# Control_board_POD_CMS.net
KiCad netlist of a schematic drawn in EAGLE
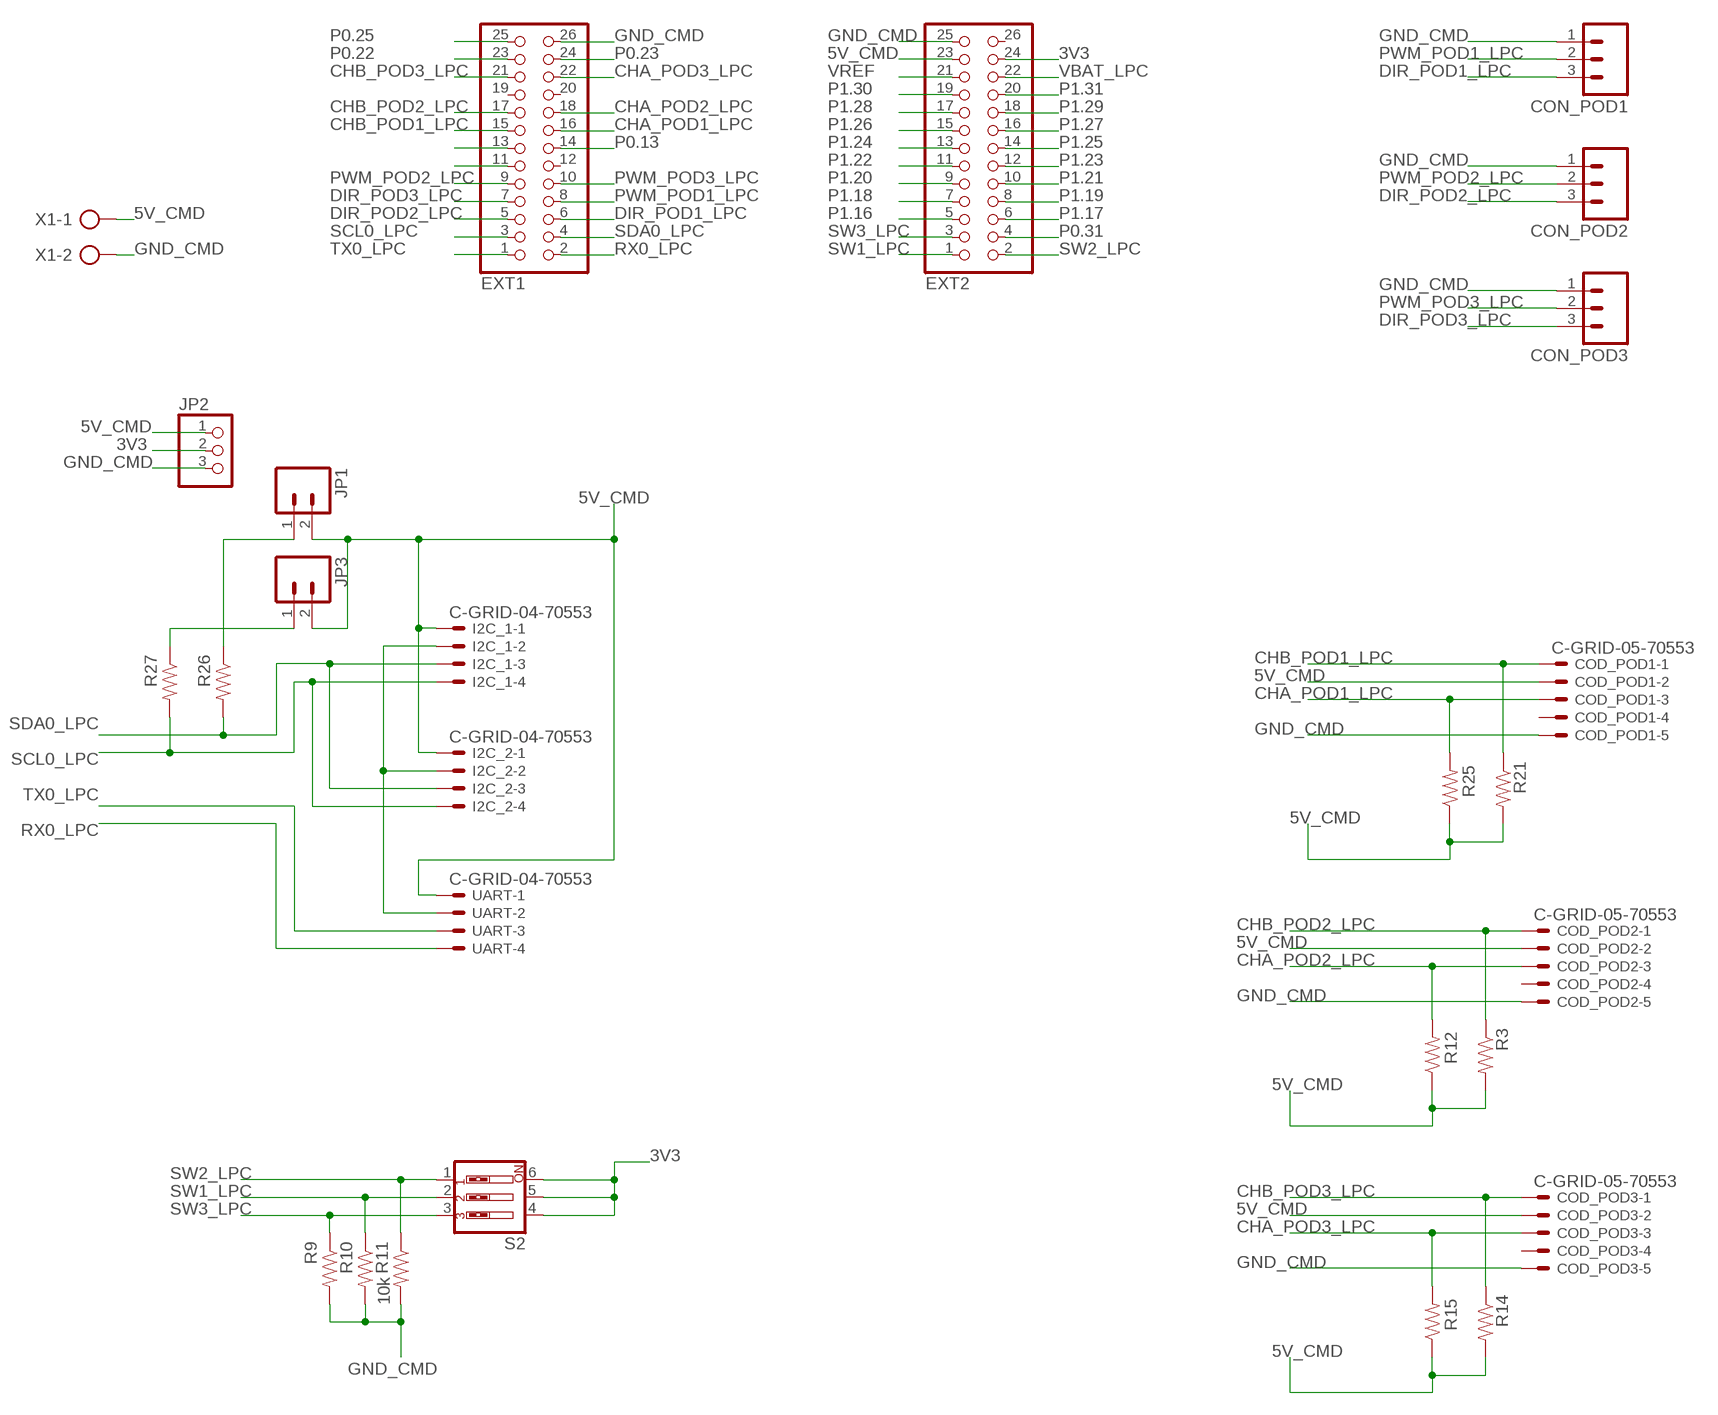
[diagram p0: schematic, sheet 1, part 1 of 2]
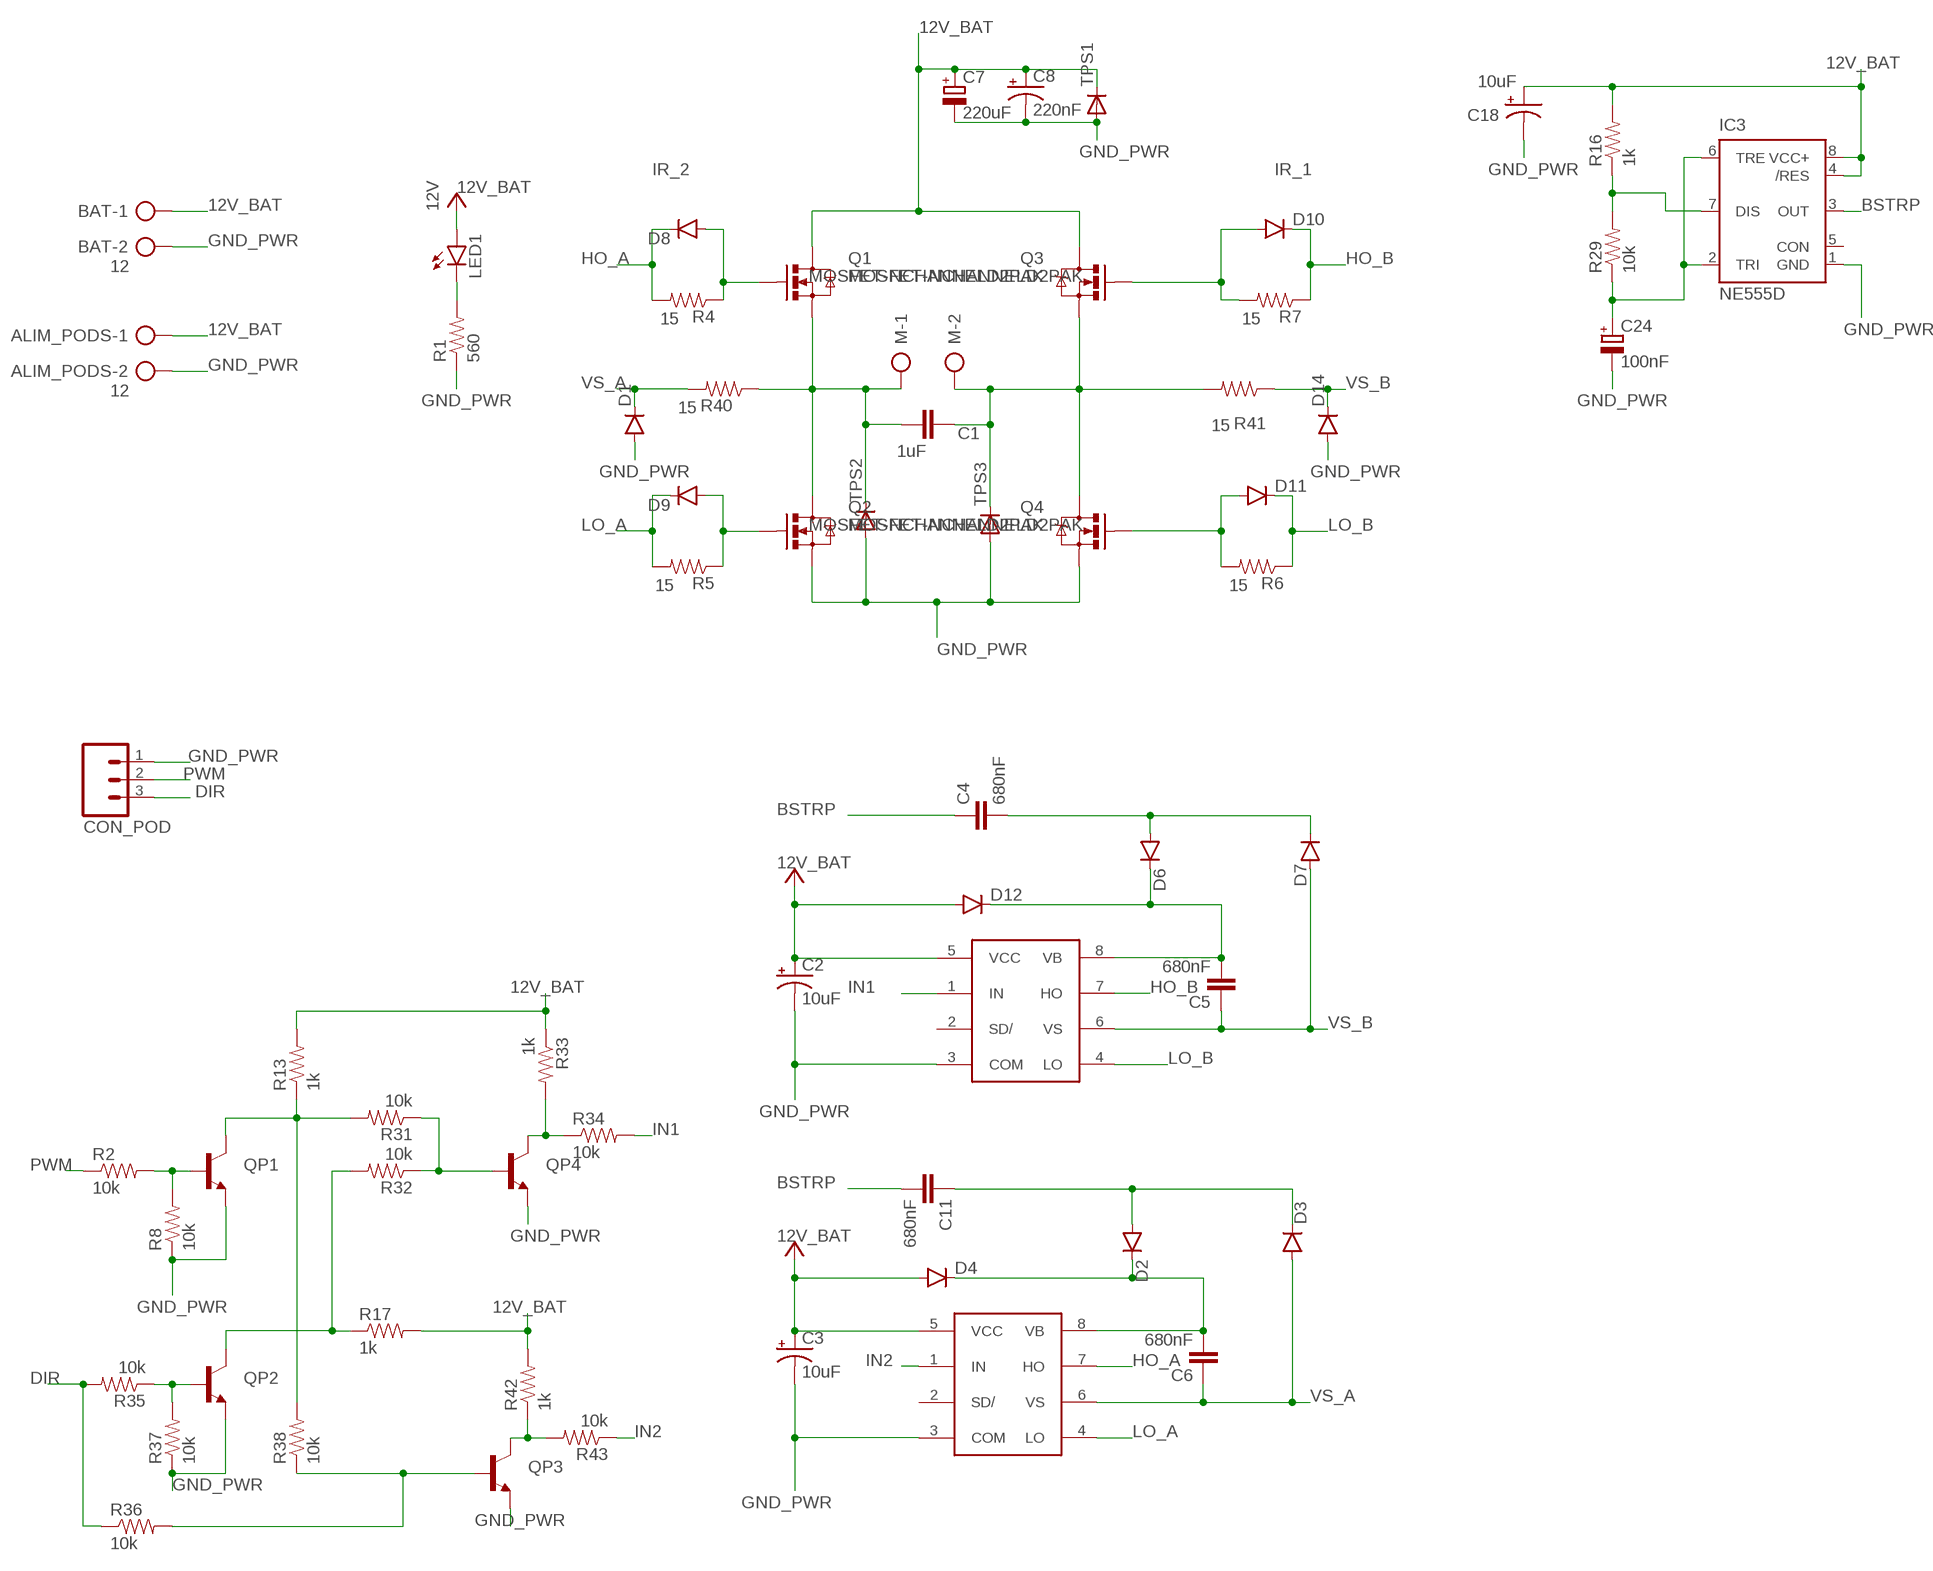
[diagram p1: schematic, sheet 1, part 2 of 2]

(export (version "E")
  (design (tool "Eeschema 10.0.6"))
  (components
    (comp (ref "ALIM_PODS")
      (value "12")
      (footprint "eagle-import:AK500_2")
      (libsource (lib "eagle-import") (part "AK500/2"))
    )
    (comp (ref "BAT")
      (value "12")
      (footprint "eagle-import:AK500_2")
      (libsource (lib "eagle-import") (part "AK500/2"))
    )
    (comp (ref "C1")
      (value "1uF")
      (footprint "eagle-import:0603-CAP")
      (libsource (lib "eagle-import") (part "CAP0603-CAP"))
    )
    (comp (ref "C2")
      (value "10uF")
      (footprint "eagle-import:EIA3216")
      (libsource (lib "eagle-import") (part "10UF-16V-10%(TANT)"))
    )
    (comp (ref "C3")
      (value "10uF")
      (footprint "eagle-import:EIA3216")
      (libsource (lib "eagle-import") (part "10UF-16V-10%(TANT)"))
    )
    (comp (ref "C4")
      (value "680nF")
      (footprint "eagle-import:0805")
      (libsource (lib "eagle-import") (part "SparkFun-Capacitors_CAP0805"))
    )
    (comp (ref "C5")
      (value "680nF")
      (footprint "eagle-import:1206")
      (libsource (lib "eagle-import") (part "SparkFun-Capacitors_CAP1206"))
    )
    (comp (ref "C6")
      (value "680nF")
      (footprint "eagle-import:1206")
      (libsource (lib "eagle-import") (part "SparkFun-Capacitors_CAP1206"))
    )
    (comp (ref "C7")
      (value "220uF")
      (footprint "eagle-import:D_7343-31R")
      (libsource (lib "eagle-import") (part "CPOL-EUD/7343-31R"))
    )
    (comp (ref "C8")
      (value "220nF")
      (footprint "eagle-import:EIA3216")
      (libsource (lib "eagle-import") (part "10UF-16V-10%(TANT)"))
    )
    (comp (ref "C11")
      (value "680nF")
      (footprint "eagle-import:0805")
      (libsource (lib "eagle-import") (part "SparkFun-Capacitors_CAP0805"))
    )
    (comp (ref "C18")
      (value "10uF")
      (footprint "eagle-import:EIA3216")
      (fields (field (name "PROD_ID") "CAP-00811"))
      (libsource (lib "eagle-import") (part "10UF-16V-10%(TANT)"))
    )
    (comp (ref "C24")
      (value "100nF")
      (footprint "eagle-import:R_2012-12R")
      (libsource (lib "eagle-import") (part "CPOL-EUR/2012-12R"))
    )
    (comp (ref "COD_POD1")
      (value "C-GRID-05-70553")
      (footprint "eagle-import:70553-05")
      (libsource (lib "eagle-import") (part "C-GRID-05-70553"))
    )
    (comp (ref "COD_POD2")
      (value "C-GRID-05-70553")
      (footprint "eagle-import:70553-05")
      (libsource (lib "eagle-import") (part "C-GRID-05-70553"))
    )
    (comp (ref "COD_POD3")
      (value "C-GRID-05-70553")
      (footprint "eagle-import:70553-05")
      (libsource (lib "eagle-import") (part "C-GRID-05-70553"))
    )
    (comp (ref "CON_POD")
      (value "M03PTH")
      (footprint "eagle-import:1X03")
      (libsource (lib "eagle-import") (part "M03PTH"))
    )
    (comp (ref "CON_POD1")
      (value "M03PTH")
      (footprint "eagle-import:1X03")
      (libsource (lib "eagle-import") (part "M03PTH"))
    )
    (comp (ref "CON_POD2")
      (value "M03PTH")
      (footprint "eagle-import:1X03")
      (libsource (lib "eagle-import") (part "M03PTH"))
    )
    (comp (ref "CON_POD3")
      (value "M03PTH")
      (footprint "eagle-import:1X03")
      (libsource (lib "eagle-import") (part "M03PTH"))
    )
    (comp (ref "D1")
      (value "DIODESOD")
      (footprint "eagle-import:SOD-323")
      (libsource (lib "eagle-import") (part "DIODESOD"))
    )
    (comp (ref "D2")
      (value "DIODESOD")
      (footprint "eagle-import:SOD-323")
      (libsource (lib "eagle-import") (part "DIODESOD"))
    )
    (comp (ref "D3")
      (value "DIODESOD")
      (footprint "eagle-import:SOD-323")
      (libsource (lib "eagle-import") (part "DIODESOD"))
    )
    (comp (ref "D4")
      (value "DIODESOD")
      (footprint "eagle-import:SOD-323")
      (libsource (lib "eagle-import") (part "DIODESOD"))
    )
    (comp (ref "D6")
      (value "DIODESOD")
      (footprint "eagle-import:SOD-323")
      (libsource (lib "eagle-import") (part "DIODESOD"))
    )
    (comp (ref "D7")
      (value "DIODESOD")
      (footprint "eagle-import:SOD-323")
      (libsource (lib "eagle-import") (part "DIODESOD"))
    )
    (comp (ref "D8")
      (value "DIODESOD")
      (footprint "eagle-import:SOD-323")
      (libsource (lib "eagle-import") (part "DIODESOD"))
    )
    (comp (ref "D9")
      (value "DIODESOD")
      (footprint "eagle-import:SOD-323")
      (libsource (lib "eagle-import") (part "DIODESOD"))
    )
    (comp (ref "D10")
      (value "DIODESOD")
      (footprint "eagle-import:SOD-323")
      (libsource (lib "eagle-import") (part "DIODESOD"))
    )
    (comp (ref "D11")
      (value "DIODESOD")
      (footprint "eagle-import:SOD-323")
      (libsource (lib "eagle-import") (part "DIODESOD"))
    )
    (comp (ref "D12")
      (value "DIODESOD")
      (footprint "eagle-import:SOD-323")
      (libsource (lib "eagle-import") (part "DIODESOD"))
    )
    (comp (ref "D14")
      (value "DIODESOD")
      (footprint "eagle-import:SOD-323")
      (libsource (lib "eagle-import") (part "DIODESOD"))
    )
    (comp (ref "EXT1")
      (value "PINHD-2X13")
      (footprint "eagle-import:2X13")
      (libsource (lib "eagle-import") (part "PINHD-2X13"))
    )
    (comp (ref "EXT2")
      (value "PINHD-2X13")
      (footprint "eagle-import:2X13")
      (libsource (lib "eagle-import") (part "PINHD-2X13"))
    )
    (comp (ref "I2C_1")
      (value "C-GRID-04-70553")
      (footprint "eagle-import:70553-04")
      (libsource (lib "eagle-import") (part "C-GRID-04-70553"))
    )
    (comp (ref "I2C_2")
      (value "C-GRID-04-70553")
      (footprint "eagle-import:70553-04")
      (libsource (lib "eagle-import") (part "C-GRID-04-70553"))
    )
    (comp (ref "IC3")
      (value "NE555D")
      (footprint "eagle-import:SO08")
      (libsource (lib "eagle-import") (part "NE555D"))
    )
    (comp (ref "IR2184SPBF1")
      (value "IR2184SPBF")
      (footprint "eagle-import:SO08")
      (libsource (lib "eagle-import") (part "IR2184SPBF"))
    )
    (comp (ref "IR2184SPBF2")
      (value "IR2184SPBF")
      (footprint "eagle-import:SO08")
      (libsource (lib "eagle-import") (part "IR2184SPBF"))
    )
    (comp (ref "JP1")
      (value "M02PTH")
      (footprint "eagle-import:1X02")
      (libsource (lib "eagle-import") (part "M02PTH"))
    )
    (comp (ref "JP2")
      (value "PINHD-1X3")
      (footprint "eagle-import:1X03")
      (libsource (lib "eagle-import") (part "PINHD-1X3"))
    )
    (comp (ref "JP3")
      (value "M02PTH")
      (footprint "eagle-import:1X02")
      (libsource (lib "eagle-import") (part "M02PTH"))
    )
    (comp (ref "LED1")
      (value "LED-WHITE")
      (footprint "eagle-import:LED-1206")
      (libsource (lib "eagle-import") (part "LED-WHITE"))
    )
    (comp (ref "M")
      (value "AK500/2")
      (footprint "eagle-import:AK500_2")
      (libsource (lib "eagle-import") (part "AK500/2"))
    )
    (comp (ref "Q1")
      (value "MOSFET-NCHANNELD2PAK")
      (footprint "eagle-import:D2PAK-3")
      (libsource (lib "eagle-import") (part "MOSFET-NCHANNELD2PAK"))
    )
    (comp (ref "Q2")
      (value "MOSFET-NCHANNELD2PAK")
      (footprint "eagle-import:D2PAK-3")
      (libsource (lib "eagle-import") (part "MOSFET-NCHANNELD2PAK"))
    )
    (comp (ref "Q3")
      (value "MOSFET-NCHANNELD2PAK")
      (footprint "eagle-import:D2PAK-3")
      (libsource (lib "eagle-import") (part "MOSFET-NCHANNELD2PAK"))
    )
    (comp (ref "Q4")
      (value "MOSFET-NCHANNELD2PAK")
      (footprint "eagle-import:D2PAK-3")
      (libsource (lib "eagle-import") (part "MOSFET-NCHANNELD2PAK"))
    )
    (comp (ref "QP1")
      (value "TRANSISTOR_NPNSOT23-3")
      (footprint "eagle-import:SOT23-3")
      (libsource (lib "eagle-import") (part "TRANSISTOR_NPNSOT23-3"))
    )
    (comp (ref "QP2")
      (value "TRANSISTOR_NPNSOT23-3")
      (footprint "eagle-import:SOT23-3")
      (libsource (lib "eagle-import") (part "TRANSISTOR_NPNSOT23-3"))
    )
    (comp (ref "QP3")
      (value "TRANSISTOR_NPNSOT23-3")
      (footprint "eagle-import:SOT23-3")
      (libsource (lib "eagle-import") (part "TRANSISTOR_NPNSOT23-3"))
    )
    (comp (ref "QP4")
      (value "TRANSISTOR_NPNSOT23-3")
      (footprint "eagle-import:SOT23-3")
      (libsource (lib "eagle-import") (part "TRANSISTOR_NPNSOT23-3"))
    )
    (comp (ref "R1")
      (value "560")
      (footprint "eagle-import:1206")
      (libsource (lib "eagle-import") (part "RESISTOR1206"))
    )
    (comp (ref "R2")
      (value "10k")
      (footprint "eagle-import:0603-RES")
      (libsource (lib "eagle-import") (part "SparkFun-Passives_RESISTOR0603-RES"))
    )
    (comp (ref "R3")
      (value "3k3")
      (footprint "eagle-import:0603-RES")
      (libsource (lib "eagle-import") (part "SparkFun-Passives_RESISTOR0603-RES"))
    )
    (comp (ref "R4")
      (value "15")
      (footprint "eagle-import:0805")
      (libsource (lib "eagle-import") (part "SparkFun-Passives_RESISTOR0805-RES"))
    )
    (comp (ref "R5")
      (value "15")
      (footprint "eagle-import:0805")
      (libsource (lib "eagle-import") (part "SparkFun-Passives_RESISTOR0805-RES"))
    )
    (comp (ref "R6")
      (value "15")
      (footprint "eagle-import:0805")
      (libsource (lib "eagle-import") (part "SparkFun-Passives_RESISTOR0805-RES"))
    )
    (comp (ref "R7")
      (value "15")
      (footprint "eagle-import:0805")
      (libsource (lib "eagle-import") (part "SparkFun-Passives_RESISTOR0805-RES"))
    )
    (comp (ref "R8")
      (value "10k")
      (footprint "eagle-import:0603-RES")
      (libsource (lib "eagle-import") (part "SparkFun-Passives_RESISTOR0603-RES"))
    )
    (comp (ref "R9")
      (value "10k")
      (footprint "eagle-import:0603-RES")
      (libsource (lib "eagle-import") (part "SparkFun-Passives_RESISTOR0603-RES"))
    )
    (comp (ref "R10")
      (value "10k")
      (footprint "eagle-import:0603-RES")
      (libsource (lib "eagle-import") (part "SparkFun-Passives_RESISTOR0603-RES"))
    )
    (comp (ref "R11")
      (value "10k")
      (footprint "eagle-import:0603-RES")
      (libsource (lib "eagle-import") (part "SparkFun-Passives_RESISTOR0603-RES"))
    )
    (comp (ref "R12")
      (value "3k3")
      (footprint "eagle-import:0603-RES")
      (libsource (lib "eagle-import") (part "SparkFun-Passives_RESISTOR0603-RES"))
    )
    (comp (ref "R13")
      (value "1k")
      (footprint "eagle-import:0603-RES")
      (libsource (lib "eagle-import") (part "SparkFun-Passives_RESISTOR0603-RES"))
    )
    (comp (ref "R14")
      (value "3k3")
      (footprint "eagle-import:0603-RES")
      (libsource (lib "eagle-import") (part "SparkFun-Passives_RESISTOR0603-RES"))
    )
    (comp (ref "R15")
      (value "3k3")
      (footprint "eagle-import:0603-RES")
      (libsource (lib "eagle-import") (part "SparkFun-Passives_RESISTOR0603-RES"))
    )
    (comp (ref "R16")
      (value "1k")
      (footprint "eagle-import:0603-RES")
      (libsource (lib "eagle-import") (part "SparkFun-Passives_RESISTOR0603-RES"))
    )
    (comp (ref "R17")
      (value "1k")
      (footprint "eagle-import:0603-RES")
      (libsource (lib "eagle-import") (part "SparkFun-Passives_RESISTOR0603-RES"))
    )
    (comp (ref "R21")
      (value "3k3")
      (footprint "eagle-import:0603-RES")
      (libsource (lib "eagle-import") (part "SparkFun-Passives_RESISTOR0603-RES"))
    )
    (comp (ref "R25")
      (value "3k3")
      (footprint "eagle-import:0603-RES")
      (libsource (lib "eagle-import") (part "SparkFun-Passives_RESISTOR0603-RES"))
    )
    (comp (ref "R26")
      (value "3.3k")
      (footprint "eagle-import:0603-RES")
      (libsource (lib "eagle-import") (part "SparkFun-Passives_RESISTOR0603-RES"))
    )
    (comp (ref "R27")
      (value "3.3k")
      (footprint "eagle-import:0603-RES")
      (libsource (lib "eagle-import") (part "SparkFun-Passives_RESISTOR0603-RES"))
    )
    (comp (ref "R29")
      (value "10k")
      (footprint "eagle-import:0603-RES")
      (libsource (lib "eagle-import") (part "SparkFun-Passives_RESISTOR0603-RES"))
    )
    (comp (ref "R31")
      (value "10k")
      (footprint "eagle-import:0603-RES")
      (libsource (lib "eagle-import") (part "SparkFun-Passives_RESISTOR0603-RES"))
    )
    (comp (ref "R32")
      (value "10k")
      (footprint "eagle-import:0603-RES")
      (libsource (lib "eagle-import") (part "SparkFun-Passives_RESISTOR0603-RES"))
    )
    (comp (ref "R33")
      (value "1k")
      (footprint "eagle-import:0603-RES")
      (libsource (lib "eagle-import") (part "SparkFun-Passives_RESISTOR0603-RES"))
    )
    (comp (ref "R34")
      (value "10k")
      (footprint "eagle-import:0603-RES")
      (libsource (lib "eagle-import") (part "SparkFun-Passives_RESISTOR0603-RES"))
    )
    (comp (ref "R35")
      (value "10k")
      (footprint "eagle-import:0603-RES")
      (libsource (lib "eagle-import") (part "SparkFun-Passives_RESISTOR0603-RES"))
    )
    (comp (ref "R36")
      (value "10k")
      (footprint "eagle-import:0603-RES")
      (libsource (lib "eagle-import") (part "SparkFun-Passives_RESISTOR0603-RES"))
    )
    (comp (ref "R37")
      (value "10k")
      (footprint "eagle-import:0603-RES")
      (libsource (lib "eagle-import") (part "SparkFun-Passives_RESISTOR0603-RES"))
    )
    (comp (ref "R38")
      (value "10k")
      (footprint "eagle-import:0603-RES")
      (libsource (lib "eagle-import") (part "SparkFun-Passives_RESISTOR0603-RES"))
    )
    (comp (ref "R40")
      (value "15")
      (footprint "eagle-import:0603-RES")
      (libsource (lib "eagle-import") (part "SparkFun-Passives_RESISTOR0603-RES"))
    )
    (comp (ref "R41")
      (value "15")
      (footprint "eagle-import:0603-RES")
      (libsource (lib "eagle-import") (part "SparkFun-Passives_RESISTOR0603-RES"))
    )
    (comp (ref "R42")
      (value "1k")
      (footprint "eagle-import:0603-RES")
      (libsource (lib "eagle-import") (part "SparkFun-Passives_RESISTOR0603-RES"))
    )
    (comp (ref "R43")
      (value "10k")
      (footprint "eagle-import:0603-RES")
      (libsource (lib "eagle-import") (part "SparkFun-Passives_RESISTOR0603-RES"))
    )
    (comp (ref "S2")
      (value "SW_DIP-3")
      (footprint "eagle-import:EDG-03")
      (libsource (lib "eagle-import") (part "SW_DIP-3"))
    )
    (comp (ref "TPS1")
      (value "DIODE-SMC")
      (footprint "eagle-import:SMC")
      (libsource (lib "eagle-import") (part "DIODE-SMC"))
    )
    (comp (ref "TPS2")
      (value "DIODE-SMC")
      (footprint "eagle-import:SMC")
      (libsource (lib "eagle-import") (part "DIODE-SMC"))
    )
    (comp (ref "TPS3")
      (value "DIODE-SMC")
      (footprint "eagle-import:SMC")
      (libsource (lib "eagle-import") (part "DIODE-SMC"))
    )
    (comp (ref "UART")
      (value "C-GRID-04-70553")
      (footprint "eagle-import:70553-04")
      (libsource (lib "eagle-import") (part "C-GRID-04-70553"))
    )
    (comp (ref "X1")
      (value "AK500/2")
      (footprint "eagle-import:AK500_2")
      (libsource (lib "eagle-import") (part "AK500/2"))
    )
  )
  (nets
    (net (code "1") (name "/3V3") (class "Default")
      (node (ref "EXT2") (pin "24") (pinfunction "24_24") (pintype "passive"))
      (node (ref "JP2") (pin "2") (pinfunction "2_2") (pintype "passive"))
      (node (ref "S2") (pin "4") (pinfunction "4_4") (pintype "passive"))
      (node (ref "S2") (pin "5") (pinfunction "5_5") (pintype "passive"))
      (node (ref "S2") (pin "6") (pinfunction "6_6") (pintype "passive"))
    )
    (net (code "2") (name "/5V_CMD") (class "Default")
      (node (ref "COD_POD1") (pin "2") (pinfunction "S_2") (pintype "passive"))
      (node (ref "COD_POD2") (pin "2") (pinfunction "S_2") (pintype "passive"))
      (node (ref "COD_POD3") (pin "2") (pinfunction "S_2") (pintype "passive"))
      (node (ref "EXT2") (pin "23") (pinfunction "23_23") (pintype "passive"))
      (node (ref "I2C_1") (pin "1") (pinfunction "S_1") (pintype "passive"))
      (node (ref "I2C_2") (pin "1") (pinfunction "S_1") (pintype "passive"))
      (node (ref "JP1") (pin "2") (pinfunction "2_2") (pintype "passive"))
      (node (ref "JP2") (pin "1") (pinfunction "1_1") (pintype "passive"))
      (node (ref "JP3") (pin "2") (pinfunction "2_2") (pintype "passive"))
      (node (ref "R12") (pin "1") (pinfunction "1_1") (pintype "passive"))
      (node (ref "R14") (pin "2") (pinfunction "2_2") (pintype "passive"))
      (node (ref "R15") (pin "1") (pinfunction "1_1") (pintype "passive"))
      (node (ref "R21") (pin "2") (pinfunction "2_2") (pintype "passive"))
      (node (ref "R25") (pin "1") (pinfunction "1_1") (pintype "passive"))
      (node (ref "R3") (pin "2") (pinfunction "2_2") (pintype "passive"))
      (node (ref "UART") (pin "1") (pinfunction "S_1") (pintype "passive"))
      (node (ref "X1") (pin "1") (pinfunction "KL_1") (pintype "passive"))
    )
    (net (code "3") (name "/BSTRP") (class "Default")
      (node (ref "C11") (pin "2") (pinfunction "2_2") (pintype "passive"))
      (node (ref "C4") (pin "1") (pinfunction "1_1") (pintype "passive"))
      (node (ref "IC3") (pin "3") (pinfunction "OUT_3") (pintype "output"))
    )
    (net (code "4") (name "/CHA_POD1_LPC") (class "Default")
      (node (ref "COD_POD1") (pin "3") (pinfunction "S_3") (pintype "passive"))
      (node (ref "EXT1") (pin "16") (pinfunction "16_16") (pintype "passive"))
      (node (ref "R25") (pin "2") (pinfunction "2_2") (pintype "passive"))
    )
    (net (code "5") (name "/CHA_POD2_LPC") (class "Default")
      (node (ref "COD_POD2") (pin "3") (pinfunction "S_3") (pintype "passive"))
      (node (ref "EXT1") (pin "18") (pinfunction "18_18") (pintype "passive"))
      (node (ref "R12") (pin "2") (pinfunction "2_2") (pintype "passive"))
    )
    (net (code "6") (name "/CHA_POD3_LPC") (class "Default")
      (node (ref "COD_POD3") (pin "3") (pinfunction "S_3") (pintype "passive"))
      (node (ref "EXT1") (pin "22") (pinfunction "22_22") (pintype "passive"))
      (node (ref "R15") (pin "2") (pinfunction "2_2") (pintype "passive"))
    )
    (net (code "7") (name "/CHB_POD1_LPC") (class "Default")
      (node (ref "COD_POD1") (pin "1") (pinfunction "S_1") (pintype "passive"))
      (node (ref "EXT1") (pin "15") (pinfunction "15_15") (pintype "passive"))
      (node (ref "R21") (pin "1") (pinfunction "1_1") (pintype "passive"))
    )
    (net (code "8") (name "/CHB_POD2_LPC") (class "Default")
      (node (ref "COD_POD2") (pin "1") (pinfunction "S_1") (pintype "passive"))
      (node (ref "EXT1") (pin "17") (pinfunction "17_17") (pintype "passive"))
      (node (ref "R3") (pin "1") (pinfunction "1_1") (pintype "passive"))
    )
    (net (code "9") (name "/CHB_POD3_LPC") (class "Default")
      (node (ref "COD_POD3") (pin "1") (pinfunction "S_1") (pintype "passive"))
      (node (ref "EXT1") (pin "21") (pinfunction "21_21") (pintype "passive"))
      (node (ref "R14") (pin "1") (pinfunction "1_1") (pintype "passive"))
    )
    (net (code "10") (name "/DIR") (class "Default")
      (node (ref "CON_POD") (pin "3") (pinfunction "3_3") (pintype "passive"))
      (node (ref "R35") (pin "2") (pinfunction "2_2") (pintype "passive"))
      (node (ref "R36") (pin "1") (pinfunction "1_1") (pintype "passive"))
    )
    (net (code "11") (name "/DIR_POD1_LPC") (class "Default")
      (node (ref "CON_POD1") (pin "3") (pinfunction "3_3") (pintype "passive"))
      (node (ref "EXT1") (pin "6") (pinfunction "6_6") (pintype "passive"))
    )
    (net (code "12") (name "/DIR_POD2_LPC") (class "Default")
      (node (ref "CON_POD2") (pin "3") (pinfunction "3_3") (pintype "passive"))
      (node (ref "EXT1") (pin "5") (pinfunction "5_5") (pintype "passive"))
    )
    (net (code "13") (name "/DIR_POD3_LPC") (class "Default")
      (node (ref "CON_POD3") (pin "3") (pinfunction "3_3") (pintype "passive"))
      (node (ref "EXT1") (pin "7") (pinfunction "7_7") (pintype "passive"))
    )
    (net (code "14") (name "/GND_CMD") (class "Default")
      (node (ref "COD_POD1") (pin "5") (pinfunction "S_5") (pintype "passive"))
      (node (ref "COD_POD2") (pin "5") (pinfunction "S_5") (pintype "passive"))
      (node (ref "COD_POD3") (pin "5") (pinfunction "S_5") (pintype "passive"))
      (node (ref "CON_POD1") (pin "1") (pinfunction "1_1") (pintype "passive"))
      (node (ref "CON_POD2") (pin "1") (pinfunction "1_1") (pintype "passive"))
      (node (ref "CON_POD3") (pin "1") (pinfunction "1_1") (pintype "passive"))
      (node (ref "EXT1") (pin "26") (pinfunction "26_26") (pintype "passive"))
      (node (ref "EXT2") (pin "25") (pinfunction "25_25") (pintype "passive"))
      (node (ref "I2C_1") (pin "2") (pinfunction "S_2") (pintype "passive"))
      (node (ref "I2C_2") (pin "2") (pinfunction "S_2") (pintype "passive"))
      (node (ref "JP2") (pin "3") (pinfunction "3_3") (pintype "passive"))
      (node (ref "R10") (pin "2") (pinfunction "2_2") (pintype "passive"))
      (node (ref "R11") (pin "2") (pinfunction "2_2") (pintype "passive"))
      (node (ref "R9") (pin "2") (pinfunction "2_2") (pintype "passive"))
      (node (ref "UART") (pin "2") (pinfunction "S_2") (pintype "passive"))
      (node (ref "X1") (pin "2") (pinfunction "KL_2") (pintype "passive"))
    )
    (net (code "15") (name "/GND_PWR") (class "Default")
      (node (ref "ALIM_PODS") (pin "2") (pinfunction "KL_2") (pintype "passive"))
      (node (ref "BAT") (pin "2") (pinfunction "KL_2") (pintype "passive"))
      (node (ref "C18") (pin "C") (pinfunction "-_C") (pintype "passive"))
      (node (ref "C2") (pin "C") (pinfunction "-_C") (pintype "passive"))
      (node (ref "C24") (pin "-") (pinfunction "-_-") (pintype "passive"))
      (node (ref "C3") (pin "C") (pinfunction "-_C") (pintype "passive"))
      (node (ref "C7") (pin "-") (pinfunction "-_-") (pintype "passive"))
      (node (ref "C8") (pin "C") (pinfunction "-_C") (pintype "passive"))
      (node (ref "CON_POD") (pin "1") (pinfunction "1_1") (pintype "passive"))
      (node (ref "D1") (pin "A") (pinfunction "A_A") (pintype "passive"))
      (node (ref "D14") (pin "A") (pinfunction "A_A") (pintype "passive"))
      (node (ref "IC3") (pin "1") (pinfunction "GND_1") (pintype "power_in"))
      (node (ref "IR2184SPBF1") (pin "3") (pinfunction "COM_3") (pintype "bidirectional"))
      (node (ref "IR2184SPBF2") (pin "3") (pinfunction "COM_3") (pintype "bidirectional"))
      (node (ref "Q2") (pin "3") (pinfunction "S_3") (pintype "passive"))
      (node (ref "Q4") (pin "3") (pinfunction "S_3") (pintype "passive"))
      (node (ref "QP1") (pin "2") (pinfunction "E_2") (pintype "passive"))
      (node (ref "QP2") (pin "2") (pinfunction "E_2") (pintype "passive"))
      (node (ref "QP3") (pin "2") (pinfunction "E_2") (pintype "passive"))
      (node (ref "QP4") (pin "2") (pinfunction "E_2") (pintype "passive"))
      (node (ref "R1") (pin "1") (pinfunction "1_1") (pintype "passive"))
      (node (ref "R37") (pin "1") (pinfunction "1_1") (pintype "passive"))
      (node (ref "R8") (pin "1") (pinfunction "1_1") (pintype "passive"))
      (node (ref "TPS1") (pin "A") (pinfunction "A_A") (pintype "passive"))
      (node (ref "TPS2") (pin "A") (pinfunction "A_A") (pintype "passive"))
      (node (ref "TPS3") (pin "A") (pinfunction "A_A") (pintype "passive"))
    )
    (net (code "16") (name "/HO_A") (class "Default")
      (node (ref "D8") (pin "C") (pinfunction "C_C") (pintype "passive"))
      (node (ref "IR2184SPBF2") (pin "7") (pinfunction "HO_7") (pintype "bidirectional"))
      (node (ref "R4") (pin "2") (pinfunction "2_2") (pintype "passive"))
    )
    (net (code "17") (name "/HO_B") (class "Default")
      (node (ref "D10") (pin "C") (pinfunction "C_C") (pintype "passive"))
      (node (ref "IR2184SPBF1") (pin "7") (pinfunction "HO_7") (pintype "bidirectional"))
      (node (ref "R7") (pin "1") (pinfunction "1_1") (pintype "passive"))
    )
    (net (code "18") (name "/IN1") (class "Default")
      (node (ref "IR2184SPBF1") (pin "1") (pinfunction "IN_1") (pintype "bidirectional"))
      (node (ref "R34") (pin "2") (pinfunction "2_2") (pintype "passive"))
    )
    (net (code "19") (name "/IN2") (class "Default")
      (node (ref "IR2184SPBF2") (pin "1") (pinfunction "IN_1") (pintype "bidirectional"))
      (node (ref "R43") (pin "1") (pinfunction "1_1") (pintype "passive"))
    )
    (net (code "20") (name "/LO_A") (class "Default")
      (node (ref "D9") (pin "C") (pinfunction "C_C") (pintype "passive"))
      (node (ref "IR2184SPBF2") (pin "4") (pinfunction "LO_4") (pintype "bidirectional"))
      (node (ref "R5") (pin "2") (pinfunction "2_2") (pintype "passive"))
    )
    (net (code "21") (name "/LO_B") (class "Default")
      (node (ref "D11") (pin "C") (pinfunction "C_C") (pintype "passive"))
      (node (ref "IR2184SPBF1") (pin "4") (pinfunction "LO_4") (pintype "bidirectional"))
      (node (ref "R6") (pin "1") (pinfunction "1_1") (pintype "passive"))
    )
    (net (code "22") (name "/P0.13") (class "Default")
      (node (ref "EXT1") (pin "14") (pinfunction "14_14") (pintype "passive"))
    )
    (net (code "23") (name "/P0.22") (class "Default")
      (node (ref "EXT1") (pin "23") (pinfunction "23_23") (pintype "passive"))
    )
    (net (code "24") (name "/P0.23") (class "Default")
      (node (ref "EXT1") (pin "24") (pinfunction "24_24") (pintype "passive"))
    )
    (net (code "25") (name "/P0.25") (class "Default")
      (node (ref "EXT1") (pin "25") (pinfunction "25_25") (pintype "passive"))
    )
    (net (code "26") (name "/P0.31") (class "Default")
      (node (ref "EXT2") (pin "4") (pinfunction "4_4") (pintype "passive"))
    )
    (net (code "27") (name "/P1.16") (class "Default")
      (node (ref "EXT2") (pin "5") (pinfunction "5_5") (pintype "passive"))
    )
    (net (code "28") (name "/P1.17") (class "Default")
      (node (ref "EXT2") (pin "6") (pinfunction "6_6") (pintype "passive"))
    )
    (net (code "29") (name "/P1.18") (class "Default")
      (node (ref "EXT2") (pin "7") (pinfunction "7_7") (pintype "passive"))
    )
    (net (code "30") (name "/P1.19") (class "Default")
      (node (ref "EXT2") (pin "8") (pinfunction "8_8") (pintype "passive"))
    )
    (net (code "31") (name "/P1.20") (class "Default")
      (node (ref "EXT2") (pin "9") (pinfunction "9_9") (pintype "passive"))
    )
    (net (code "32") (name "/P1.21") (class "Default")
      (node (ref "EXT2") (pin "10") (pinfunction "10_10") (pintype "passive"))
    )
    (net (code "33") (name "/P1.22") (class "Default")
      (node (ref "EXT2") (pin "11") (pinfunction "11_11") (pintype "passive"))
    )
    (net (code "34") (name "/P1.23") (class "Default")
      (node (ref "EXT2") (pin "12") (pinfunction "12_12") (pintype "passive"))
    )
    (net (code "35") (name "/P1.24") (class "Default")
      (node (ref "EXT2") (pin "13") (pinfunction "13_13") (pintype "passive"))
    )
    (net (code "36") (name "/P1.25") (class "Default")
      (node (ref "EXT2") (pin "14") (pinfunction "14_14") (pintype "passive"))
    )
    (net (code "37") (name "/P1.26") (class "Default")
      (node (ref "EXT2") (pin "15") (pinfunction "15_15") (pintype "passive"))
    )
    (net (code "38") (name "/P1.27") (class "Default")
      (node (ref "EXT2") (pin "16") (pinfunction "16_16") (pintype "passive"))
    )
    (net (code "39") (name "/P1.28") (class "Default")
      (node (ref "EXT2") (pin "17") (pinfunction "17_17") (pintype "passive"))
    )
    (net (code "40") (name "/P1.29") (class "Default")
      (node (ref "EXT2") (pin "18") (pinfunction "18_18") (pintype "passive"))
    )
    (net (code "41") (name "/P1.30") (class "Default")
      (node (ref "EXT2") (pin "19") (pinfunction "19_19") (pintype "passive"))
    )
    (net (code "42") (name "/P1.31") (class "Default")
      (node (ref "EXT2") (pin "20") (pinfunction "20_20") (pintype "passive"))
    )
    (net (code "43") (name "/PWM") (class "Default")
      (node (ref "CON_POD") (pin "2") (pinfunction "2_2") (pintype "passive"))
      (node (ref "R2") (pin "1") (pinfunction "1_1") (pintype "passive"))
    )
    (net (code "44") (name "/PWM_POD1_LPC") (class "Default")
      (node (ref "CON_POD1") (pin "2") (pinfunction "2_2") (pintype "passive"))
      (node (ref "EXT1") (pin "8") (pinfunction "8_8") (pintype "passive"))
    )
    (net (code "45") (name "/PWM_POD2_LPC") (class "Default")
      (node (ref "CON_POD2") (pin "2") (pinfunction "2_2") (pintype "passive"))
      (node (ref "EXT1") (pin "9") (pinfunction "9_9") (pintype "passive"))
    )
    (net (code "46") (name "/PWM_POD3_LPC") (class "Default")
      (node (ref "CON_POD3") (pin "2") (pinfunction "2_2") (pintype "passive"))
      (node (ref "EXT1") (pin "10") (pinfunction "10_10") (pintype "passive"))
    )
    (net (code "47") (name "/RX0_LPC") (class "Default")
      (node (ref "EXT1") (pin "2") (pinfunction "2_2") (pintype "passive"))
      (node (ref "UART") (pin "4") (pinfunction "S_4") (pintype "passive"))
    )
    (net (code "48") (name "/SCL0_LPC") (class "Default")
      (node (ref "EXT1") (pin "3") (pinfunction "3_3") (pintype "passive"))
      (node (ref "I2C_1") (pin "4") (pinfunction "S_4") (pintype "passive"))
      (node (ref "I2C_2") (pin "4") (pinfunction "S_4") (pintype "passive"))
      (node (ref "R27") (pin "2") (pinfunction "2_2") (pintype "passive"))
    )
    (net (code "49") (name "/SDA0_LPC") (class "Default")
      (node (ref "EXT1") (pin "4") (pinfunction "4_4") (pintype "passive"))
      (node (ref "I2C_1") (pin "3") (pinfunction "S_3") (pintype "passive"))
      (node (ref "I2C_2") (pin "3") (pinfunction "S_3") (pintype "passive"))
      (node (ref "R26") (pin "2") (pinfunction "2_2") (pintype "passive"))
    )
    (net (code "50") (name "/SW1_LPC") (class "Default")
      (node (ref "EXT2") (pin "1") (pinfunction "1_1") (pintype "passive"))
      (node (ref "R10") (pin "1") (pinfunction "1_1") (pintype "passive"))
      (node (ref "S2") (pin "2") (pinfunction "2_2") (pintype "passive"))
    )
    (net (code "51") (name "/SW2_LPC") (class "Default")
      (node (ref "EXT2") (pin "2") (pinfunction "2_2") (pintype "passive"))
      (node (ref "R11") (pin "1") (pinfunction "1_1") (pintype "passive"))
      (node (ref "S2") (pin "1") (pinfunction "1_1") (pintype "passive"))
    )
    (net (code "52") (name "/SW3_LPC") (class "Default")
      (node (ref "EXT2") (pin "3") (pinfunction "3_3") (pintype "passive"))
      (node (ref "R9") (pin "1") (pinfunction "1_1") (pintype "passive"))
      (node (ref "S2") (pin "3") (pinfunction "3_3") (pintype "passive"))
    )
    (net (code "53") (name "/TX0_LPC") (class "Default")
      (node (ref "EXT1") (pin "1") (pinfunction "1_1") (pintype "passive"))
      (node (ref "UART") (pin "3") (pinfunction "S_3") (pintype "passive"))
    )
    (net (code "54") (name "/VBAT_LPC") (class "Default")
      (node (ref "EXT2") (pin "22") (pinfunction "22_22") (pintype "passive"))
    )
    (net (code "55") (name "/VREF") (class "Default")
      (node (ref "EXT2") (pin "21") (pinfunction "21_21") (pintype "passive"))
    )
    (net (code "56") (name "/VS_A") (class "Default")
      (node (ref "C6") (pin "1") (pinfunction "1_1") (pintype "passive"))
      (node (ref "D1") (pin "C") (pinfunction "C_C") (pintype "passive"))
      (node (ref "D3") (pin "A") (pinfunction "A_A") (pintype "passive"))
      (node (ref "IR2184SPBF2") (pin "6") (pinfunction "VS_6") (pintype "bidirectional"))
      (node (ref "R40") (pin "2") (pinfunction "2_2") (pintype "passive"))
    )
    (net (code "57") (name "/VS_B") (class "Default")
      (node (ref "C5") (pin "1") (pinfunction "1_1") (pintype "passive"))
      (node (ref "D14") (pin "C") (pinfunction "C_C") (pintype "passive"))
      (node (ref "D7") (pin "A") (pinfunction "A_A") (pintype "passive"))
      (node (ref "IR2184SPBF1") (pin "6") (pinfunction "VS_6") (pintype "bidirectional"))
      (node (ref "R41") (pin "1") (pinfunction "1_1") (pintype "passive"))
    )
    (net (code "58") (name "12V") (class "Default")
      (node (ref "ALIM_PODS") (pin "1") (pinfunction "KL_1") (pintype "passive"))
      (node (ref "BAT") (pin "1") (pinfunction "KL_1") (pintype "passive"))
      (node (ref "C18") (pin "A") (pinfunction "+_A") (pintype "passive"))
      (node (ref "C2") (pin "A") (pinfunction "+_A") (pintype "passive"))
      (node (ref "C3") (pin "A") (pinfunction "+_A") (pintype "passive"))
      (node (ref "C7") (pin "+") (pinfunction "+_+") (pintype "passive"))
      (node (ref "C8") (pin "A") (pinfunction "+_A") (pintype "passive"))
      (node (ref "D12") (pin "A") (pinfunction "A_A") (pintype "passive"))
      (node (ref "D4") (pin "A") (pinfunction "A_A") (pintype "passive"))
      (node (ref "IC3") (pin "4") (pinfunction "/RES_4") (pintype "input"))
      (node (ref "IC3") (pin "8") (pinfunction "VCC+_8") (pintype "power_in"))
      (node (ref "IR2184SPBF1") (pin "5") (pinfunction "VCC_5") (pintype "bidirectional"))
      (node (ref "IR2184SPBF2") (pin "5") (pinfunction "VCC_5") (pintype "bidirectional"))
      (node (ref "LED1") (pin "A") (pinfunction "A_A") (pintype "passive"))
      (node (ref "Q1") (pin "4") (pinfunction "D_4") (pintype "passive"))
      (node (ref "Q3") (pin "4") (pinfunction "D_4") (pintype "passive"))
      (node (ref "R13") (pin "2") (pinfunction "2_2") (pintype "passive"))
      (node (ref "R16") (pin "2") (pinfunction "2_2") (pintype "passive"))
      (node (ref "R17") (pin "2") (pinfunction "2_2") (pintype "passive"))
      (node (ref "R33") (pin "1") (pinfunction "1_1") (pintype "passive"))
      (node (ref "R42") (pin "2") (pinfunction "2_2") (pintype "passive"))
      (node (ref "TPS1") (pin "C") (pinfunction "C_C") (pintype "passive"))
    )
    (net (code "59") (name "Net-(C4-Pad2)") (class "Default")
      (node (ref "C4") (pin "2") (pinfunction "2_2") (pintype "passive"))
      (node (ref "D6") (pin "A") (pinfunction "A_A") (pintype "passive"))
      (node (ref "D7") (pin "C") (pinfunction "C_C") (pintype "passive"))
    )
    (net (code "60") (name "Net-(C11-Pad1)") (class "Default")
      (node (ref "C11") (pin "1") (pinfunction "1_1") (pintype "passive"))
      (node (ref "D2") (pin "A") (pinfunction "A_A") (pintype "passive"))
      (node (ref "D3") (pin "C") (pinfunction "C_C") (pintype "passive"))
    )
    (net (code "61") (name "Net-(IC3-DIS)") (class "Default")
      (node (ref "IC3") (pin "7") (pinfunction "DIS_7") (pintype "input"))
      (node (ref "R16") (pin "1") (pinfunction "1_1") (pintype "passive"))
      (node (ref "R29") (pin "2") (pinfunction "2_2") (pintype "passive"))
    )
    (net (code "62") (name "Net-(IC3-TRE)") (class "Default")
      (node (ref "C24") (pin "+") (pinfunction "+_+") (pintype "passive"))
      (node (ref "IC3") (pin "2") (pinfunction "TRI_2") (pintype "input"))
      (node (ref "IC3") (pin "6") (pinfunction "TRE_6") (pintype "input"))
      (node (ref "R29") (pin "1") (pinfunction "1_1") (pintype "passive"))
    )
    (net (code "63") (name "Net-(IR2184SPBF1-VB)") (class "Default")
      (node (ref "C5") (pin "2") (pinfunction "2_2") (pintype "passive"))
      (node (ref "D12") (pin "C") (pinfunction "C_C") (pintype "passive"))
      (node (ref "D6") (pin "C") (pinfunction "C_C") (pintype "passive"))
      (node (ref "IR2184SPBF1") (pin "8") (pinfunction "VB_8") (pintype "bidirectional"))
    )
    (net (code "64") (name "Net-(IR2184SPBF2-VB)") (class "Default")
      (node (ref "C6") (pin "2") (pinfunction "2_2") (pintype "passive"))
      (node (ref "D2") (pin "C") (pinfunction "C_C") (pintype "passive"))
      (node (ref "D4") (pin "C") (pinfunction "C_C") (pintype "passive"))
      (node (ref "IR2184SPBF2") (pin "8") (pinfunction "VB_8") (pintype "bidirectional"))
    )
    (net (code "65") (name "Net-(JP1-Pad1)") (class "Default")
      (node (ref "JP1") (pin "1") (pinfunction "1_1") (pintype "passive"))
      (node (ref "R26") (pin "1") (pinfunction "1_1") (pintype "passive"))
    )
    (net (code "66") (name "Net-(JP3-Pad1)") (class "Default")
      (node (ref "JP3") (pin "1") (pinfunction "1_1") (pintype "passive"))
      (node (ref "R27") (pin "1") (pinfunction "1_1") (pintype "passive"))
    )
    (net (code "67") (name "Net-(LED1-PadC)") (class "Default")
      (node (ref "LED1") (pin "C") (pinfunction "C_C") (pintype "passive"))
      (node (ref "R1") (pin "2") (pinfunction "2_2") (pintype "passive"))
    )
    (net (code "68") (name "Net-(MA-KL)") (class "Default")
      (node (ref "C1") (pin "1") (pinfunction "1_1") (pintype "passive"))
      (node (ref "M") (pin "1") (pinfunction "KL_1") (pintype "passive"))
      (node (ref "Q1") (pin "3") (pinfunction "S_3") (pintype "passive"))
      (node (ref "Q2") (pin "4") (pinfunction "D_4") (pintype "passive"))
      (node (ref "R40") (pin "1") (pinfunction "1_1") (pintype "passive"))
      (node (ref "TPS2") (pin "C") (pinfunction "C_C") (pintype "passive"))
    )
    (net (code "69") (name "Net-(MB-KL)") (class "Default")
      (node (ref "C1") (pin "2") (pinfunction "2_2") (pintype "passive"))
      (node (ref "M") (pin "2") (pinfunction "KL_2") (pintype "passive"))
      (node (ref "Q3") (pin "3") (pinfunction "S_3") (pintype "passive"))
      (node (ref "Q4") (pin "4") (pinfunction "D_4") (pintype "passive"))
      (node (ref "R41") (pin "2") (pinfunction "2_2") (pintype "passive"))
      (node (ref "TPS3") (pin "C") (pinfunction "C_C") (pintype "passive"))
    )
    (net (code "70") (name "Net-(Q1-G)") (class "Default")
      (node (ref "D8") (pin "A") (pinfunction "A_A") (pintype "passive"))
      (node (ref "Q1") (pin "1") (pinfunction "G_1") (pintype "passive"))
      (node (ref "R4") (pin "1") (pinfunction "1_1") (pintype "passive"))
    )
    (net (code "71") (name "Net-(Q2-G)") (class "Default")
      (node (ref "D9") (pin "A") (pinfunction "A_A") (pintype "passive"))
      (node (ref "Q2") (pin "1") (pinfunction "G_1") (pintype "passive"))
      (node (ref "R5") (pin "1") (pinfunction "1_1") (pintype "passive"))
    )
    (net (code "72") (name "Net-(Q3-G)") (class "Default")
      (node (ref "D10") (pin "A") (pinfunction "A_A") (pintype "passive"))
      (node (ref "Q3") (pin "1") (pinfunction "G_1") (pintype "passive"))
      (node (ref "R7") (pin "2") (pinfunction "2_2") (pintype "passive"))
    )
    (net (code "73") (name "Net-(Q4-G)") (class "Default")
      (node (ref "D11") (pin "A") (pinfunction "A_A") (pintype "passive"))
      (node (ref "Q4") (pin "1") (pinfunction "G_1") (pintype "passive"))
      (node (ref "R6") (pin "2") (pinfunction "2_2") (pintype "passive"))
    )
    (net (code "74") (name "Net-(QP1-B)") (class "Default")
      (node (ref "QP1") (pin "1") (pinfunction "B_1") (pintype "passive"))
      (node (ref "R2") (pin "2") (pinfunction "2_2") (pintype "passive"))
      (node (ref "R8") (pin "2") (pinfunction "2_2") (pintype "passive"))
    )
    (net (code "75") (name "Net-(QP1-C)") (class "Default")
      (node (ref "QP1") (pin "3") (pinfunction "C_3") (pintype "passive"))
      (node (ref "R13") (pin "1") (pinfunction "1_1") (pintype "passive"))
      (node (ref "R31") (pin "2") (pinfunction "2_2") (pintype "passive"))
      (node (ref "R38") (pin "2") (pinfunction "2_2") (pintype "passive"))
    )
    (net (code "76") (name "Net-(QP2-B)") (class "Default")
      (node (ref "QP2") (pin "1") (pinfunction "B_1") (pintype "passive"))
      (node (ref "R35") (pin "1") (pinfunction "1_1") (pintype "passive"))
      (node (ref "R37") (pin "2") (pinfunction "2_2") (pintype "passive"))
    )
    (net (code "77") (name "Net-(QP2-C)") (class "Default")
      (node (ref "QP2") (pin "3") (pinfunction "C_3") (pintype "passive"))
      (node (ref "R17") (pin "1") (pinfunction "1_1") (pintype "passive"))
      (node (ref "R32") (pin "2") (pinfunction "2_2") (pintype "passive"))
    )
    (net (code "78") (name "Net-(QP3-B)") (class "Default")
      (node (ref "QP3") (pin "1") (pinfunction "B_1") (pintype "passive"))
      (node (ref "R36") (pin "2") (pinfunction "2_2") (pintype "passive"))
      (node (ref "R38") (pin "1") (pinfunction "1_1") (pintype "passive"))
    )
    (net (code "79") (name "Net-(QP3-C)") (class "Default")
      (node (ref "QP3") (pin "3") (pinfunction "C_3") (pintype "passive"))
      (node (ref "R42") (pin "1") (pinfunction "1_1") (pintype "passive"))
      (node (ref "R43") (pin "2") (pinfunction "2_2") (pintype "passive"))
    )
    (net (code "80") (name "Net-(QP4-B)") (class "Default")
      (node (ref "QP4") (pin "1") (pinfunction "B_1") (pintype "passive"))
      (node (ref "R31") (pin "1") (pinfunction "1_1") (pintype "passive"))
      (node (ref "R32") (pin "1") (pinfunction "1_1") (pintype "passive"))
    )
    (net (code "81") (name "Net-(QP4-C)") (class "Default")
      (node (ref "QP4") (pin "3") (pinfunction "C_3") (pintype "passive"))
      (node (ref "R33") (pin "2") (pinfunction "2_2") (pintype "passive"))
      (node (ref "R34") (pin "1") (pinfunction "1_1") (pintype "passive"))
    )
    (net (code "82") (name "unconnected-(COD_POD1D-S-Pad4)") (class "Default")
      (node (ref "COD_POD1") (pin "4") (pinfunction "S_4") (pintype "passive"))
    )
    (net (code "83") (name "unconnected-(COD_POD2D-S-Pad4)") (class "Default")
      (node (ref "COD_POD2") (pin "4") (pinfunction "S_4") (pintype "passive"))
    )
    (net (code "84") (name "unconnected-(COD_POD3D-S-Pad4)") (class "Default")
      (node (ref "COD_POD3") (pin "4") (pinfunction "S_4") (pintype "passive"))
    )
    (net (code "85") (name "unconnected-(EXT1-Pad11)") (class "Default")
      (node (ref "EXT1") (pin "11") (pinfunction "11_11") (pintype "passive"))
    )
    (net (code "86") (name "unconnected-(EXT1-Pad12)") (class "Default")
      (node (ref "EXT1") (pin "12") (pinfunction "12_12") (pintype "passive"))
    )
    (net (code "87") (name "unconnected-(EXT1-Pad13)") (class "Default")
      (node (ref "EXT1") (pin "13") (pinfunction "13_13") (pintype "passive"))
    )
    (net (code "88") (name "unconnected-(EXT1-Pad19)") (class "Default")
      (node (ref "EXT1") (pin "19") (pinfunction "19_19") (pintype "passive"))
    )
    (net (code "89") (name "unconnected-(EXT1-Pad20)") (class "Default")
      (node (ref "EXT1") (pin "20") (pinfunction "20_20") (pintype "passive"))
    )
    (net (code "90") (name "unconnected-(EXT2-Pad26)") (class "Default")
      (node (ref "EXT2") (pin "26") (pinfunction "26_26") (pintype "passive"))
    )
    (net (code "91") (name "unconnected-(IC3-CON-Pad5)") (class "Default")
      (node (ref "IC3") (pin "5") (pinfunction "CON_5") (pintype "input"))
    )
    (net (code "92") (name "unconnected-(IR2184SPBF1-SD{slash}-Pad2)") (class "Default")
      (node (ref "IR2184SPBF1") (pin "2") (pinfunction "SD/_2") (pintype "bidirectional"))
    )
    (net (code "93") (name "unconnected-(IR2184SPBF2-SD{slash}-Pad2)") (class "Default")
      (node (ref "IR2184SPBF2") (pin "2") (pinfunction "SD/_2") (pintype "bidirectional"))
    )
  )
)
